# SCH-Orange_PI_Power_Hat_Sheet_1_Altium.net
KiCad netlist of a schematic drawn in Altium Designer
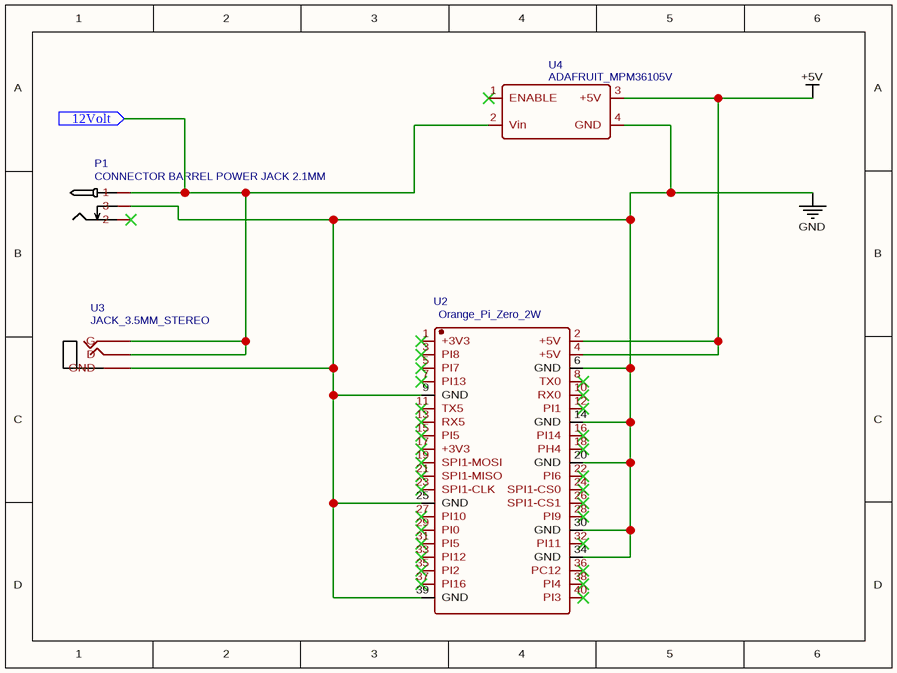
[diagram p0: SCH-Orange_PI_Power_Hat_Sheet_1_Altium.schdoc]

(export (version "E")
  (design (tool "Eeschema 10.0.6"))
  (components
    (comp (ref "P1")
      (value "CONNECTOR BARREL POWER JACK 2.1MM")
      (fields (field (name "CONTRIBUTOR") "Jan-Haase18"))
      (libsource (lib "altium-import") (part "root_0_CONNECTOR BARREL POWER JACK 2.1MM_"))
    )
    (comp (ref "U2")
      (value "Orange_Pi_Zero_2W")
      (fields
        (field (name "MANUFACTURER PART") "Raspberry Pi Zero W V1.3")
        (field (name "CONTRIBUTOR") "gillfish101")
      )
      (libsource (lib "altium-import") (part "root_0_Orange_Pi_Zero_2W_"))
    )
    (comp (ref "U3")
      (value "JACK_3.5MM_STEREO")
      (fields
        (field (name "MANUFACTURER PART") "ST-029 AUDIO JACK 3.5mm")
        (field (name "CONTRIBUTOR") "jaouad")
      )
      (libsource (lib "altium-import") (part "root_0_JACK_3.5MM_STEREO_"))
    )
    (comp (ref "U4")
      (value "ADAFRUIT_MPM36105V")
      (fields (field (name "CONTRIBUTOR") "Aidan Farley"))
      (libsource (lib "altium-import") (part "root_0_ADAFRUIT_MPM36105V_"))
    )
  )
  (nets
    (net (code "1") (name "+5V") (class "Default")
      (node (ref "U2") (pin "2") (pinfunction "+5V_2") (pintype "passive"))
      (node (ref "U2") (pin "4") (pinfunction "+5V_4") (pintype "passive"))
      (node (ref "U4") (pin "3") (pinfunction "+5V_3") (pintype "passive"))
    )
    (net (code "2") (name "/12Volt") (class "Default")
      (node (ref "P1") (pin "1") (pinfunction "1_1") (pintype "passive"))
      (node (ref "U3") (pin "1") (pinfunction "G_1") (pintype "passive"))
      (node (ref "U3") (pin "2") (pinfunction "D_2") (pintype "passive"))
      (node (ref "U4") (pin "2") (pinfunction "Vin_2") (pintype "passive"))
    )
    (net (code "3") (name "GND") (class "Default")
      (node (ref "P1") (pin "3") (pinfunction "3_3") (pintype "passive"))
      (node (ref "U2") (pin "14") (pinfunction "GND_14") (pintype "passive"))
      (node (ref "U2") (pin "20") (pinfunction "GND_20") (pintype "passive"))
      (node (ref "U2") (pin "25") (pinfunction "GND_25") (pintype "passive"))
      (node (ref "U2") (pin "30") (pinfunction "GND_30") (pintype "passive"))
      (node (ref "U2") (pin "34") (pinfunction "GND_34") (pintype "passive"))
      (node (ref "U2") (pin "39") (pinfunction "GND_39") (pintype "passive"))
      (node (ref "U2") (pin "6") (pinfunction "GND_6") (pintype "passive"))
      (node (ref "U2") (pin "9") (pinfunction "GND_9") (pintype "passive"))
      (node (ref "U3") (pin "3") (pinfunction "GND_3") (pintype "passive"))
      (node (ref "U4") (pin "4") (pinfunction "GND_4") (pintype "passive"))
    )
    (net (code "4") (name "unconnected-(P1-Pad2)") (class "Default")
      (node (ref "P1") (pin "2") (pinfunction "2_2") (pintype "passive+no_connect"))
    )
    (net (code "5") (name "unconnected-(U2-+3V3-Pad1)") (class "Default")
      (node (ref "U2") (pin "1") (pinfunction "+3V3_1") (pintype "passive+no_connect"))
    )
    (net (code "6") (name "unconnected-(U2-+3V3-Pad17)") (class "Default")
      (node (ref "U2") (pin "17") (pinfunction "+3V3_17") (pintype "passive+no_connect"))
    )
    (net (code "7") (name "unconnected-(U2-PC12-Pad36)") (class "Default")
      (node (ref "U2") (pin "36") (pinfunction "PC12_36") (pintype "passive+no_connect"))
    )
    (net (code "8") (name "unconnected-(U2-PH4-Pad18)") (class "Default")
      (node (ref "U2") (pin "18") (pinfunction "PH4_18") (pintype "passive+no_connect"))
    )
    (net (code "9") (name "unconnected-(U2-PI0-Pad29)") (class "Default")
      (node (ref "U2") (pin "29") (pinfunction "PI0_29") (pintype "passive+no_connect"))
    )
    (net (code "10") (name "unconnected-(U2-PI1-Pad12)") (class "Default")
      (node (ref "U2") (pin "12") (pinfunction "PI1_12") (pintype "passive+no_connect"))
    )
    (net (code "11") (name "unconnected-(U2-PI2-Pad35)") (class "Default")
      (node (ref "U2") (pin "35") (pinfunction "PI2_35") (pintype "passive+no_connect"))
    )
    (net (code "12") (name "unconnected-(U2-PI3-Pad40)") (class "Default")
      (node (ref "U2") (pin "40") (pinfunction "PI3_40") (pintype "passive+no_connect"))
    )
    (net (code "13") (name "unconnected-(U2-PI4-Pad38)") (class "Default")
      (node (ref "U2") (pin "38") (pinfunction "PI4_38") (pintype "passive+no_connect"))
    )
    (net (code "14") (name "unconnected-(U2-PI5-Pad15)") (class "Default")
      (node (ref "U2") (pin "15") (pinfunction "PI5_15") (pintype "passive+no_connect"))
    )
    (net (code "15") (name "unconnected-(U2-PI5-Pad31)") (class "Default")
      (node (ref "U2") (pin "31") (pinfunction "PI5_31") (pintype "passive+no_connect"))
    )
    (net (code "16") (name "unconnected-(U2-PI6-Pad22)") (class "Default")
      (node (ref "U2") (pin "22") (pinfunction "PI6_22") (pintype "passive+no_connect"))
    )
    (net (code "17") (name "unconnected-(U2-PI7-Pad5)") (class "Default")
      (node (ref "U2") (pin "5") (pinfunction "PI7_5") (pintype "passive+no_connect"))
    )
    (net (code "18") (name "unconnected-(U2-PI8-Pad3)") (class "Default")
      (node (ref "U2") (pin "3") (pinfunction "PI8_3") (pintype "passive+no_connect"))
    )
    (net (code "19") (name "unconnected-(U2-PI9-Pad28)") (class "Default")
      (node (ref "U2") (pin "28") (pinfunction "PI9_28") (pintype "passive+no_connect"))
    )
    (net (code "20") (name "unconnected-(U2-PI10-Pad27)") (class "Default")
      (node (ref "U2") (pin "27") (pinfunction "PI10_27") (pintype "passive+no_connect"))
    )
    (net (code "21") (name "unconnected-(U2-PI11-Pad32)") (class "Default")
      (node (ref "U2") (pin "32") (pinfunction "PI11_32") (pintype "passive+no_connect"))
    )
    (net (code "22") (name "unconnected-(U2-PI12-Pad33)") (class "Default")
      (node (ref "U2") (pin "33") (pinfunction "PI12_33") (pintype "passive+no_connect"))
    )
    (net (code "23") (name "unconnected-(U2-PI13-Pad7)") (class "Default")
      (node (ref "U2") (pin "7") (pinfunction "PI13_7") (pintype "passive+no_connect"))
    )
    (net (code "24") (name "unconnected-(U2-PI14-Pad16)") (class "Default")
      (node (ref "U2") (pin "16") (pinfunction "PI14_16") (pintype "passive+no_connect"))
    )
    (net (code "25") (name "unconnected-(U2-PI16-Pad37)") (class "Default")
      (node (ref "U2") (pin "37") (pinfunction "PI16_37") (pintype "passive+no_connect"))
    )
    (net (code "26") (name "unconnected-(U2-RX0-Pad10)") (class "Default")
      (node (ref "U2") (pin "10") (pinfunction "RX0_10") (pintype "passive+no_connect"))
    )
    (net (code "27") (name "unconnected-(U2-RX5-Pad13)") (class "Default")
      (node (ref "U2") (pin "13") (pinfunction "RX5_13") (pintype "passive+no_connect"))
    )
    (net (code "28") (name "unconnected-(U2-SPI1-CLK-Pad23)") (class "Default")
      (node (ref "U2") (pin "23") (pinfunction "SPI1-CLK_23") (pintype "passive+no_connect"))
    )
    (net (code "29") (name "unconnected-(U2-SPI1-CS0-Pad24)") (class "Default")
      (node (ref "U2") (pin "24") (pinfunction "SPI1-CS0_24") (pintype "passive+no_connect"))
    )
    (net (code "30") (name "unconnected-(U2-SPI1-CS1-Pad26)") (class "Default")
      (node (ref "U2") (pin "26") (pinfunction "SPI1-CS1_26") (pintype "passive+no_connect"))
    )
    (net (code "31") (name "unconnected-(U2-SPI1-MISO-Pad21)") (class "Default")
      (node (ref "U2") (pin "21") (pinfunction "SPI1-MISO_21") (pintype "passive+no_connect"))
    )
    (net (code "32") (name "unconnected-(U2-SPI1-MOSI-Pad19)") (class "Default")
      (node (ref "U2") (pin "19") (pinfunction "SPI1-MOSI_19") (pintype "passive+no_connect"))
    )
    (net (code "33") (name "unconnected-(U2-TX0-Pad8)") (class "Default")
      (node (ref "U2") (pin "8") (pinfunction "TX0_8") (pintype "passive+no_connect"))
    )
    (net (code "34") (name "unconnected-(U2-TX5-Pad11)") (class "Default")
      (node (ref "U2") (pin "11") (pinfunction "TX5_11") (pintype "passive+no_connect"))
    )
    (net (code "35") (name "unconnected-(U4-ENABLE-Pad1)") (class "Default")
      (node (ref "U4") (pin "1") (pinfunction "ENABLE_1") (pintype "passive+no_connect"))
    )
  )
)
